# MainBoard_V100_ON_OFF.net
KiCad netlist of a schematic drawn in Altium Designer
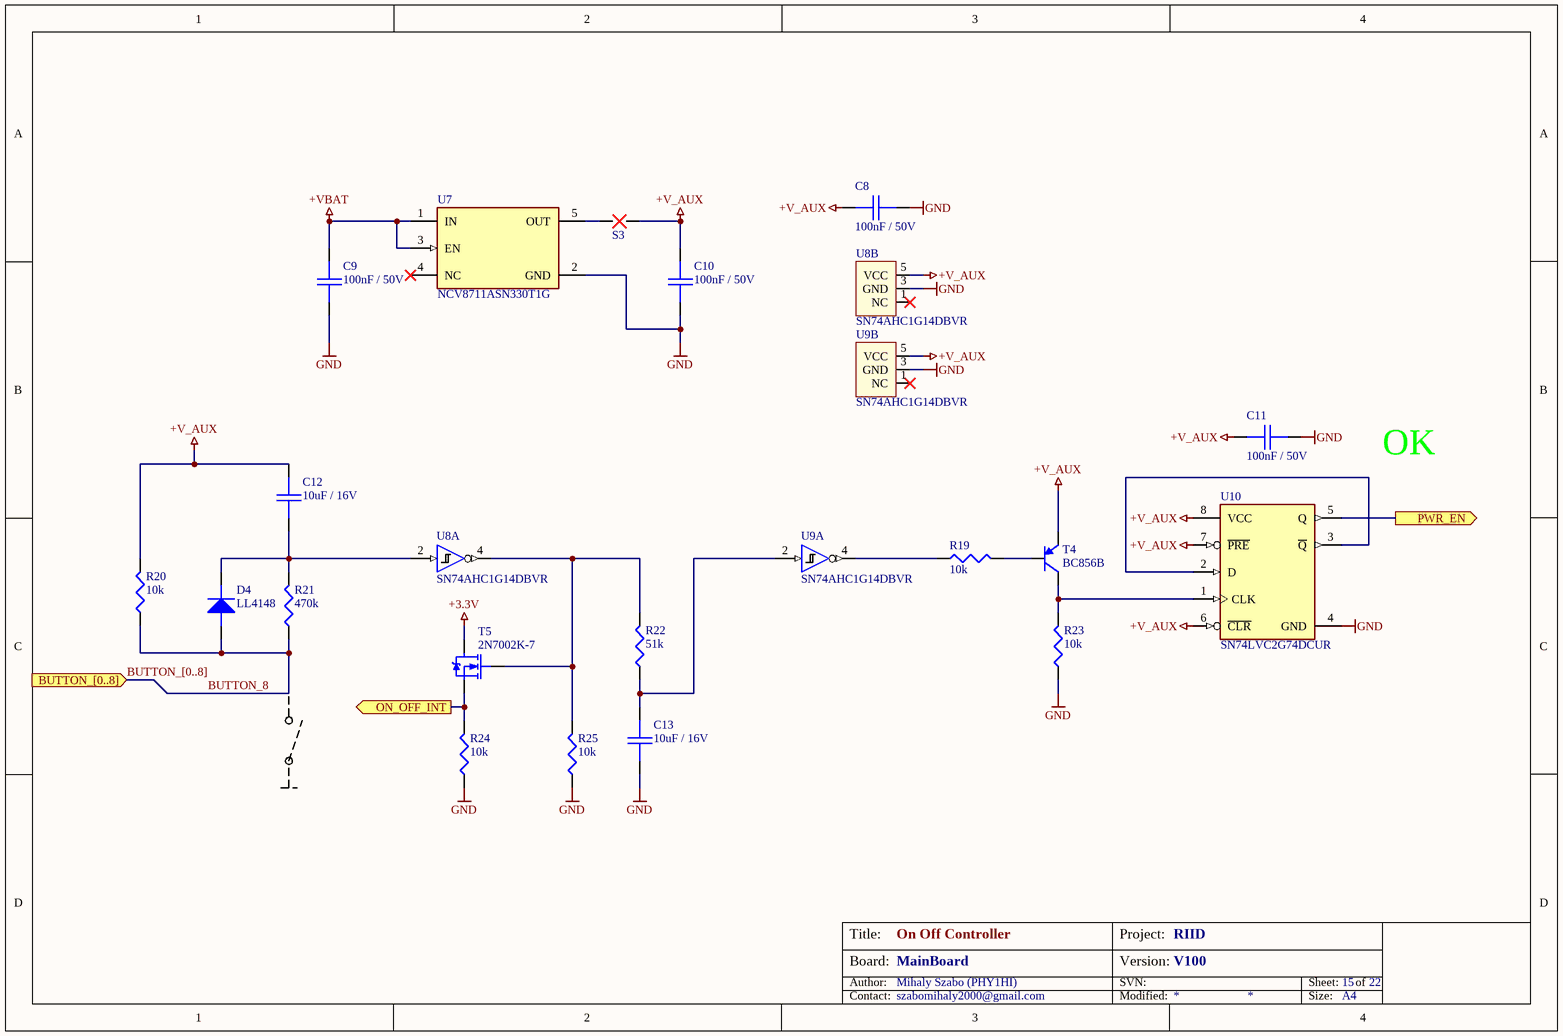
[diagram p0: MainBoard_V100_ON_OFF.SchDoc]

(export (version "E")
  (design (tool "Eeschema 10.0.6"))
  (components
    (comp (ref "C8")
      (value "100nF / 50V")
      (footprint "0805_C")
      (description "100nF 50V X7R")
      (fields (field (name "PART NUMBER") "SMD0805-100nF-50V"))
      (libsource (lib "ALTIUM_DB_LIB") (part "CAP_NONPOL"))
    )
    (comp (ref "C9")
      (value "100nF / 50V")
      (footprint "0805_C")
      (description "100nF 50V X7R")
      (fields (field (name "PART NUMBER") "SMD0805-100nF-50V"))
      (libsource (lib "ALTIUM_DB_LIB") (part "CAP_NONPOL"))
    )
    (comp (ref "C10")
      (value "100nF / 50V")
      (footprint "0805_C")
      (description "100nF 50V X7R")
      (fields (field (name "PART NUMBER") "SMD0805-100nF-50V"))
      (libsource (lib "ALTIUM_DB_LIB") (part "CAP_NONPOL"))
    )
    (comp (ref "C11")
      (value "100nF / 50V")
      (footprint "0805_C")
      (description "100nF 50V X7R")
      (fields (field (name "PART NUMBER") "SMD0805-100nF-50V"))
      (libsource (lib "ALTIUM_DB_LIB") (part "CAP_NONPOL"))
    )
    (comp (ref "C12")
      (value "10uF / 16V")
      (footprint "0805_C")
      (description "10uF 16V X5R")
      (fields (field (name "PART NUMBER") "SMD0805-10uF-16V"))
      (libsource (lib "ALTIUM_DB_LIB") (part "CAP_NONPOL"))
    )
    (comp (ref "C13")
      (value "10uF / 16V")
      (footprint "0805_C")
      (description "10uF 16V X5R")
      (fields (field (name "PART NUMBER") "SMD0805-10uF-16V"))
      (libsource (lib "ALTIUM_DB_LIB") (part "CAP_NONPOL"))
    )
    (comp (ref "D4")
      (value "LL4148")
      (footprint "SOD80")
      (description "General Purpose, Power, Switching Small Signal Diode, SOD-80, 100V, 0.15A, 175C")
      (libsource (lib "ALTIUM_DB_LIB") (part "DIODE"))
    )
    (comp (ref "R19")
      (value "10k")
      (footprint "0805")
      (description "10k 0805 0.125W 1%")
      (fields (field (name "PART NUMBER") "SMD0805-10k 1%"))
      (libsource (lib "ALTIUM_DB_LIB") (part "RESISTOR"))
    )
    (comp (ref "R20")
      (value "10k")
      (footprint "0805")
      (description "10k 0805 0.125W 1%")
      (fields (field (name "PART NUMBER") "SMD0805-10k 1%"))
      (libsource (lib "ALTIUM_DB_LIB") (part "RESISTOR"))
    )
    (comp (ref "R21")
      (value "470k")
      (footprint "0805")
      (description "470k 0805 0.125W 1%")
      (fields (field (name "PART NUMBER") "SMD0805-470k 1%"))
      (libsource (lib "ALTIUM_DB_LIB") (part "RESISTOR"))
    )
    (comp (ref "R22")
      (value "51k")
      (footprint "0805")
      (description "51k 0805 0.125W 5%")
      (fields (field (name "PART NUMBER") "SMD0805-51k 5%"))
      (libsource (lib "ALTIUM_DB_LIB") (part "RESISTOR"))
    )
    (comp (ref "R23")
      (value "10k")
      (footprint "0805")
      (description "10k 0805 0.125W 1%")
      (fields (field (name "PART NUMBER") "SMD0805-10k 1%"))
      (libsource (lib "ALTIUM_DB_LIB") (part "RESISTOR"))
    )
    (comp (ref "R24")
      (value "10k")
      (footprint "0805")
      (description "10k 0805 0.125W 1%")
      (fields (field (name "PART NUMBER") "SMD0805-10k 1%"))
      (libsource (lib "ALTIUM_DB_LIB") (part "RESISTOR"))
    )
    (comp (ref "R25")
      (value "10k")
      (footprint "0805")
      (description "10k 0805 0.125W 1%")
      (fields (field (name "PART NUMBER") "SMD0805-10k 1%"))
      (libsource (lib "ALTIUM_DB_LIB") (part "RESISTOR"))
    )
    (comp (ref "S3")
      (value "SPLITER")
      (footprint "SPLITER2_30mil_9mil")
      (description "SPLITER2_30mil_9mil")
      (libsource (lib "ALTIUM_DB_LIB") (part "SPLITER"))
    )
    (comp (ref "T4")
      (value "BC856B")
      (footprint "SOT-23")
      (description "BC856B Bipolar (BJT) Single Transistor, PNP, 65 V, 100 mA, 250 mW, SOT-23, Surface Mount")
      (libsource (lib "ALTIUM_DB_LIB") (part "BJT_PNP"))
    )
    (comp (ref "T5")
      (value "2N7002K-7")
      (footprint "SOT-23")
      (description "2N7002K-7 Power MOSFET, N Channel, 60 V, 300 mA, 2 ohm, SOT-23, Surface Mount")
      (libsource (lib "ALTIUM_DB_LIB") (part "MOSFET_N_CH"))
    )
    (comp (ref "U7")
      (value "NCV8711ASN330T1G")
      (footprint "TSOP-5")
      (description "LDO Regulator, 100 mA, 18 V, 1 uA IQ, with PG 3V3 TSOP5")
      (libsource (lib "ALTIUM_DB_LIB") (part "NCV8711ASN500T1G"))
    )
    (comp (ref "U8")
      (value "SN74AHC1G14DBVR")
      (footprint "SOT-23-5")
      (description "Single Inverting Schmitt-Trigger")
      (libsource (lib "ALTIUM_DB_LIB") (part "SN74AHC1G14DBVR"))
    )
    (comp (ref "U9")
      (value "SN74AHC1G14DBVR")
      (footprint "SOT-23-5")
      (description "Single Inverting Schmitt-Trigger")
      (libsource (lib "ALTIUM_DB_LIB") (part "SN74AHC1G14DBVR"))
    )
    (comp (ref "U10")
      (value "SN74LVC2G74DCUR")
      (footprint "VSSOP-8_DCU")
      (description "Flip-Flop, 74LVC74, D, 4.1 ns, 200 MHz, 32 mA, VSSOP")
      (libsource (lib "ALTIUM_DB_LIB") (part "SN74LVC2G74DCUR"))
    )
  )
  (nets
    (net (code "9") (name "+3.3V") (class "Default")
      (node (ref "T5") (pin "3") (pinfunction "D_3") (pintype "passive"))
    )
    (net (code "10") (name "+VBAT") (class "Default")
      (node (ref "C9") (pin "2") (pintype "passive"))
      (node (ref "U7") (pin "1") (pinfunction "IN_1") (pintype "power_in"))
      (node (ref "U7") (pin "3") (pinfunction "EN_3") (pintype "input"))
    )
    (net (code "11") (name "+V_AUX") (class "Default")
      (node (ref "C10") (pin "2") (pintype "passive"))
      (node (ref "C11") (pin "1") (pintype "passive"))
      (node (ref "C12") (pin "1") (pintype "passive"))
      (node (ref "C8") (pin "1") (pintype "passive"))
      (node (ref "R20") (pin "2") (pintype "passive"))
      (node (ref "S3") (pin "2") (pinfunction "2_2") (pintype "passive"))
      (node (ref "T4") (pin "2") (pinfunction "E_2") (pintype "passive"))
      (node (ref "U10") (pin "6") (pinfunction "~{CLR}_6") (pintype "input"))
      (node (ref "U10") (pin "7") (pinfunction "~{PRE}_7") (pintype "input"))
      (node (ref "U10") (pin "8") (pinfunction "VCC_8") (pintype "power_in"))
      (node (ref "U8") (pin "5") (pinfunction "VCC_5") (pintype "power_in"))
      (node (ref "U9") (pin "5") (pinfunction "VCC_5") (pintype "power_in"))
    )
    (net (code "12") (name "/BUTTON_8") (class "Default")
      (node (ref "D4") (pin "A") (pinfunction "A_A") (pintype "passive"))
      (node (ref "R20") (pin "1") (pintype "passive"))
      (node (ref "R21") (pin "1") (pintype "passive"))
    )
    (net (code "14") (name "/ON_OFF_INT") (class "Default")
      (node (ref "R24") (pin "2") (pintype "passive"))
      (node (ref "T5") (pin "2") (pinfunction "S_2") (pintype "passive"))
    )
    (net (code "15") (name "/PWR_EN") (class "Default")
      (node (ref "U10") (pin "5") (pinfunction "Q_5") (pintype "output"))
    )
    (net (code "16") (name "GND") (class "Default")
      (node (ref "C10") (pin "1") (pintype "passive"))
      (node (ref "C11") (pin "2") (pintype "passive"))
      (node (ref "C13") (pin "2") (pintype "passive"))
      (node (ref "C8") (pin "2") (pintype "passive"))
      (node (ref "C9") (pin "1") (pintype "passive"))
      (node (ref "R23") (pin "1") (pintype "passive"))
      (node (ref "R24") (pin "1") (pintype "passive"))
      (node (ref "R25") (pin "1") (pintype "passive"))
      (node (ref "U10") (pin "4") (pinfunction "GND_4") (pintype "power_in"))
      (node (ref "U7") (pin "2") (pinfunction "GND_2") (pintype "power_in"))
      (node (ref "U8") (pin "3") (pinfunction "GND_3") (pintype "power_in"))
      (node (ref "U9") (pin "3") (pinfunction "GND_3") (pintype "power_in"))
    )
    (net (code "17") (name "Net-(T4-B)") (class "Default")
      (node (ref "R19") (pin "2") (pintype "passive"))
      (node (ref "T4") (pin "1") (pinfunction "B_1") (pintype "passive"))
    )
    (net (code "18") (name "Net-(T4-C)") (class "Default")
      (node (ref "R23") (pin "2") (pintype "passive"))
      (node (ref "T4") (pin "3") (pinfunction "C_3") (pintype "passive"))
      (node (ref "U10") (pin "1") (pinfunction "CLK_1") (pintype "input"))
    )
    (net (code "19") (name "Net-(T5-G)") (class "Default")
      (node (ref "R22") (pin "2") (pintype "passive"))
      (node (ref "R25") (pin "2") (pintype "passive"))
      (node (ref "T5") (pin "1") (pinfunction "G_1") (pintype "passive"))
      (node (ref "U8") (pin "4") (pinfunction "Y_4") (pintype "output"))
    )
    (net (code "20") (name "Net-(U7-OUT)") (class "Default")
      (node (ref "S3") (pin "1") (pinfunction "1_1") (pintype "passive"))
      (node (ref "U7") (pin "5") (pinfunction "OUT_5") (pintype "passive"))
    )
    (net (code "21") (name "Net-(U8A-A)") (class "Default")
      (node (ref "C12") (pin "2") (pintype "passive"))
      (node (ref "D4") (pin "K") (pinfunction "K_K") (pintype "passive"))
      (node (ref "R21") (pin "2") (pintype "passive"))
      (node (ref "U8") (pin "2") (pinfunction "A_2") (pintype "input"))
    )
    (net (code "22") (name "Net-(U9A-A)") (class "Default")
      (node (ref "C13") (pin "1") (pintype "passive"))
      (node (ref "R22") (pin "1") (pintype "passive"))
      (node (ref "U9") (pin "2") (pinfunction "A_2") (pintype "input"))
    )
    (net (code "23") (name "Net-(U9A-Y)") (class "Default")
      (node (ref "R19") (pin "1") (pintype "passive"))
      (node (ref "U9") (pin "4") (pinfunction "Y_4") (pintype "output"))
    )
    (net (code "24") (name "Net-(U10-D)") (class "Default")
      (node (ref "U10") (pin "2") (pinfunction "D_2") (pintype "input"))
      (node (ref "U10") (pin "3") (pinfunction "~{Q}_3") (pintype "output"))
    )
    (net (code "25") (name "unconnected-(U7-NC-Pad4)") (class "Default")
      (node (ref "U7") (pin "4") (pinfunction "NC_4") (pintype "passive+no_connect"))
    )
    (net (code "26") (name "unconnected-(U8B-NC-Pad1)") (class "Default")
      (node (ref "U8") (pin "1") (pinfunction "NC_1") (pintype "passive+no_connect"))
    )
    (net (code "27") (name "unconnected-(U9B-NC-Pad1)") (class "Default")
      (node (ref "U9") (pin "1") (pinfunction "NC_1") (pintype "passive+no_connect"))
    )
  )
)
